# board_f-01.net
KiCad netlist of a schematic drawn in EAGLE
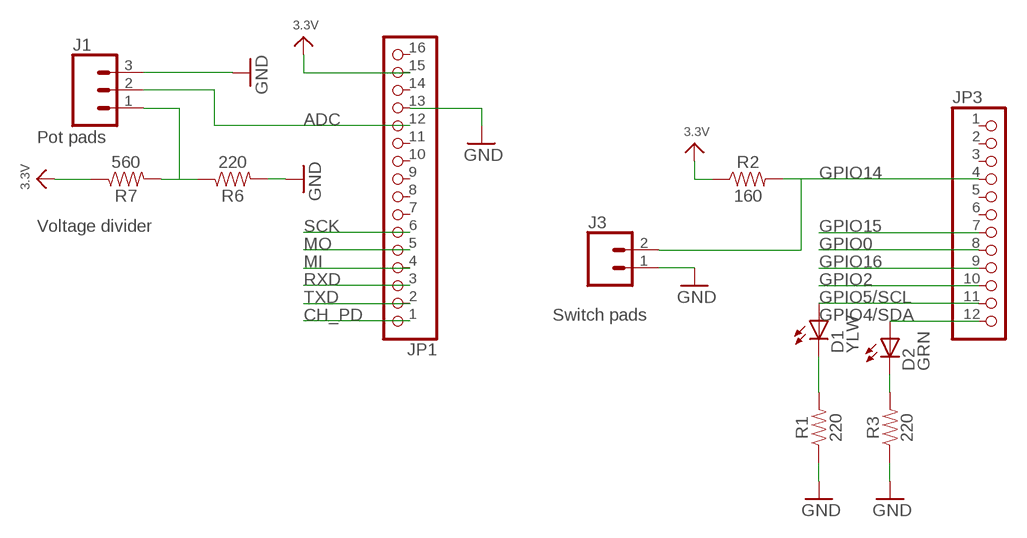
[diagram p0: schematic, sheet 1]

(export (version "E")
  (design (tool "Eeschema 10.0.6"))
  (components
    (comp (ref "D1")
      (value "YLW")
      (footprint "eagle-import:LED3MM")
      (libsource (lib "eagle-import") (part "LED3MM"))
    )
    (comp (ref "D2")
      (value "GRN")
      (footprint "eagle-import:LED3MM")
      (libsource (lib "eagle-import") (part "LED3MM"))
    )
    (comp (ref "J1")
      (value "CONN_03LOCK_LONGPADS")
      (footprint "eagle-import:1X03_LOCK_LONGPADS")
      (libsource (lib "eagle-import") (part "CONN_03LOCK_LONGPADS"))
    )
    (comp (ref "J3")
      (value "CONN_02LOCK_LONGPADS")
      (footprint "eagle-import:1X02_LOCK_LONGPADS")
      (libsource (lib "eagle-import") (part "CONN_02LOCK_LONGPADS"))
    )
    (comp (ref "JP1")
      (value "HEADER-1X16ROUND")
      (footprint "eagle-import:1X16_ROUND")
      (libsource (lib "eagle-import") (part "HEADER-1X16ROUND"))
    )
    (comp (ref "JP3")
      (value "HEADER-1X12")
      (footprint "eagle-import:1X12_ROUND")
      (libsource (lib "eagle-import") (part "HEADER-1X12"))
    )
    (comp (ref "R1")
      (value "220")
      (footprint "eagle-import:AXIAL-0.3")
      (libsource (lib "eagle-import") (part "1KOHM-HORIZ-1/4W-1%"))
    )
    (comp (ref "R2")
      (value "160")
      (footprint "eagle-import:AXIAL-0.3")
      (libsource (lib "eagle-import") (part "1KOHM-HORIZ-1/4W-1%"))
    )
    (comp (ref "R3")
      (value "220")
      (footprint "eagle-import:AXIAL-0.3")
      (libsource (lib "eagle-import") (part "1KOHM-HORIZ-1/4W-1%"))
    )
    (comp (ref "R6")
      (value "220")
      (footprint "eagle-import:AXIAL-0.3")
      (libsource (lib "eagle-import") (part "1KOHM-HORIZ-1/4W-1%"))
    )
    (comp (ref "R7")
      (value "560")
      (footprint "eagle-import:AXIAL-0.3")
      (libsource (lib "eagle-import") (part "1KOHM-HORIZ-1/4W-1%"))
    )
  )
  (nets
    (net (code "1") (name "/ADC") (class "Default")
      (node (ref "J1") (pin "2") (pinfunction "2_2") (pintype "passive"))
      (node (ref "JP1") (pin "12") (pinfunction "12_12") (pintype "passive"))
    )
    (net (code "2") (name "/CH_PD") (class "Default")
      (node (ref "JP1") (pin "1") (pinfunction "1_1") (pintype "passive"))
    )
    (net (code "3") (name "/GPIO0") (class "Default")
      (node (ref "JP3") (pin "8") (pinfunction "8_8") (pintype "passive"))
    )
    (net (code "4") (name "/GPIO2") (class "Default")
      (node (ref "JP3") (pin "10") (pinfunction "10_10") (pintype "passive"))
    )
    (net (code "5") (name "/GPIO4{slash}SDA") (class "Default")
      (node (ref "D2") (pin "A") (pinfunction "A_A") (pintype "passive"))
      (node (ref "JP3") (pin "12") (pinfunction "12_12") (pintype "passive"))
    )
    (net (code "6") (name "/GPIO5{slash}SCL") (class "Default")
      (node (ref "D1") (pin "A") (pinfunction "A_A") (pintype "passive"))
      (node (ref "JP3") (pin "11") (pinfunction "11_11") (pintype "passive"))
    )
    (net (code "7") (name "/GPIO14") (class "Default")
      (node (ref "J3") (pin "2") (pinfunction "2_2") (pintype "passive"))
      (node (ref "JP3") (pin "4") (pinfunction "4_4") (pintype "passive"))
      (node (ref "R2") (pin "P$2") (pinfunction "2_P$2") (pintype "passive"))
    )
    (net (code "8") (name "/GPIO15") (class "Default")
      (node (ref "JP3") (pin "7") (pinfunction "7_7") (pintype "passive"))
    )
    (net (code "9") (name "/GPIO16") (class "Default")
      (node (ref "JP3") (pin "9") (pinfunction "9_9") (pintype "passive"))
    )
    (net (code "10") (name "/MI") (class "Default")
      (node (ref "JP1") (pin "4") (pinfunction "4_4") (pintype "passive"))
    )
    (net (code "11") (name "/MO") (class "Default")
      (node (ref "JP1") (pin "5") (pinfunction "5_5") (pintype "passive"))
    )
    (net (code "12") (name "/RXD") (class "Default")
      (node (ref "JP1") (pin "3") (pinfunction "3_3") (pintype "passive"))
    )
    (net (code "13") (name "/SCK") (class "Default")
      (node (ref "JP1") (pin "6") (pinfunction "6_6") (pintype "passive"))
    )
    (net (code "14") (name "/TXD") (class "Default")
      (node (ref "JP1") (pin "2") (pinfunction "2_2") (pintype "passive"))
    )
    (net (code "15") (name "3.3V") (class "Default")
      (node (ref "JP1") (pin "15") (pinfunction "15_15") (pintype "passive"))
      (node (ref "R2") (pin "P$1") (pinfunction "1_P$1") (pintype "passive"))
      (node (ref "R7") (pin "P$1") (pinfunction "1_P$1") (pintype "passive"))
    )
    (net (code "16") (name "GND") (class "Default")
      (node (ref "J1") (pin "3") (pinfunction "3_3") (pintype "passive"))
      (node (ref "J3") (pin "1") (pinfunction "1_1") (pintype "passive"))
      (node (ref "JP1") (pin "13") (pinfunction "13_13") (pintype "passive"))
      (node (ref "R1") (pin "P$1") (pinfunction "1_P$1") (pintype "passive"))
      (node (ref "R3") (pin "P$1") (pinfunction "1_P$1") (pintype "passive"))
      (node (ref "R6") (pin "P$2") (pinfunction "2_P$2") (pintype "passive"))
    )
    (net (code "17") (name "Net-(D1-C)") (class "Default")
      (node (ref "D1") (pin "K") (pinfunction "C_K") (pintype "passive"))
      (node (ref "R1") (pin "P$2") (pinfunction "2_P$2") (pintype "passive"))
    )
    (net (code "18") (name "Net-(D2-C)") (class "Default")
      (node (ref "D2") (pin "K") (pinfunction "C_K") (pintype "passive"))
      (node (ref "R3") (pin "P$2") (pinfunction "2_P$2") (pintype "passive"))
    )
    (net (code "19") (name "Net-(R6-1)") (class "Default")
      (node (ref "J1") (pin "1") (pinfunction "1_1") (pintype "passive"))
      (node (ref "R6") (pin "P$1") (pinfunction "1_P$1") (pintype "passive"))
      (node (ref "R7") (pin "P$2") (pinfunction "2_P$2") (pintype "passive"))
    )
    (net (code "20") (name "unconnected-(JP1-Pad7)") (class "Default")
      (node (ref "JP1") (pin "7") (pinfunction "7_7") (pintype "passive"))
    )
    (net (code "21") (name "unconnected-(JP1-Pad8)") (class "Default")
      (node (ref "JP1") (pin "8") (pinfunction "8_8") (pintype "passive"))
    )
    (net (code "22") (name "unconnected-(JP1-Pad9)") (class "Default")
      (node (ref "JP1") (pin "9") (pinfunction "9_9") (pintype "passive"))
    )
    (net (code "23") (name "unconnected-(JP1-Pad10)") (class "Default")
      (node (ref "JP1") (pin "10") (pinfunction "10_10") (pintype "passive"))
    )
    (net (code "24") (name "unconnected-(JP1-Pad11)") (class "Default")
      (node (ref "JP1") (pin "11") (pinfunction "11_11") (pintype "passive"))
    )
    (net (code "25") (name "unconnected-(JP1-Pad14)") (class "Default")
      (node (ref "JP1") (pin "14") (pinfunction "14_14") (pintype "passive"))
    )
    (net (code "26") (name "unconnected-(JP1-Pad16)") (class "Default")
      (node (ref "JP1") (pin "16") (pinfunction "16_16") (pintype "passive"))
    )
    (net (code "27") (name "unconnected-(JP3-Pad1)") (class "Default")
      (node (ref "JP3") (pin "1") (pinfunction "1_1") (pintype "passive"))
    )
    (net (code "28") (name "unconnected-(JP3-Pad2)") (class "Default")
      (node (ref "JP3") (pin "2") (pinfunction "2_2") (pintype "passive"))
    )
    (net (code "29") (name "unconnected-(JP3-Pad3)") (class "Default")
      (node (ref "JP3") (pin "3") (pinfunction "3_3") (pintype "passive"))
    )
    (net (code "30") (name "unconnected-(JP3-Pad5)") (class "Default")
      (node (ref "JP3") (pin "5") (pinfunction "5_5") (pintype "passive"))
    )
    (net (code "31") (name "unconnected-(JP3-Pad6)") (class "Default")
      (node (ref "JP3") (pin "6") (pinfunction "6_6") (pintype "passive"))
    )
  )
)
